# schematic_christmas_tree.net
KiCad netlist of a schematic drawn in Altium Designer
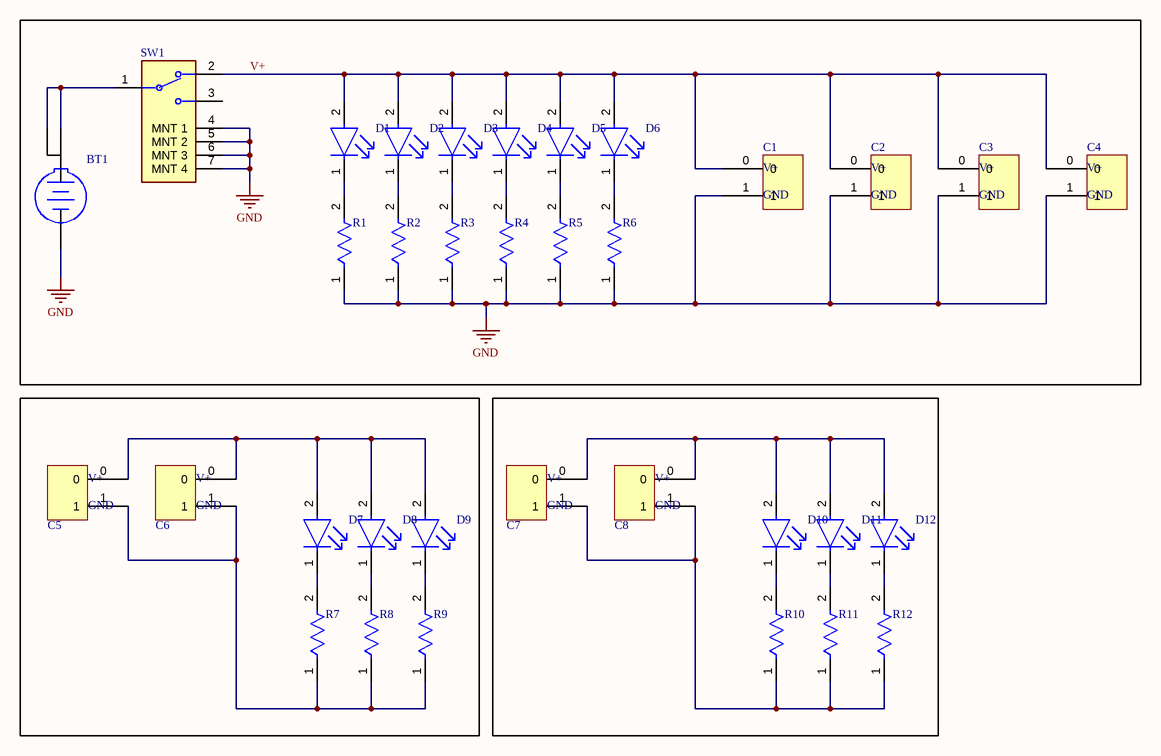
[diagram p0: schematic_christmas_tree.SchDoc]

(export (version "E")
  (design (tool "Eeschema 10.0.6"))
  (components
    (comp (ref "BT1")
      (value "3001")
      (footprint "KSTN-3001_V")
      (description "Holder Battery Coin, 12 mm, 2-Pin THD, RoHS")
      (fields (field (name "MANUFACTURER") "Keystone"))
      (libsource (lib "Altium Content Vault") (part "BATTERY-HOLDER-COIN-3"))
    )
    (comp (ref "C1")
      (value "conn_pcb")
      (footprint "pcb_connector")
      (libsource (lib "connectors") (part "conn_pcb"))
    )
    (comp (ref "C2")
      (value "conn_pcb")
      (footprint "pcb_connector")
      (libsource (lib "connectors") (part "conn_pcb"))
    )
    (comp (ref "C3")
      (value "conn_pcb")
      (footprint "pcb_connector")
      (libsource (lib "connectors") (part "conn_pcb"))
    )
    (comp (ref "C4")
      (value "conn_pcb")
      (footprint "pcb_connector")
      (libsource (lib "connectors") (part "conn_pcb"))
    )
    (comp (ref "C5") (value "conn_pcb") (footprint "pcb_connector") (libsource (lib "") (part "conn_pcb_1")))
    (comp (ref "C6") (value "conn_pcb") (footprint "pcb_connector") (libsource (lib "") (part "conn_pcb_1")))
    (comp (ref "C7") (value "conn_pcb") (footprint "pcb_connector") (libsource (lib "") (part "conn_pcb_1")))
    (comp (ref "C8") (value "conn_pcb") (footprint "pcb_connector") (libsource (lib "") (part "conn_pcb_1")))
    (comp (ref "D1")
      (value "APHCM2012SYCK-F01")
      (footprint "FP-APHCM2012SYCK-F01-MFG")
      (description "LED YELLOW CLEAR CHIP SMD")
      (libsource (lib "Altium Content Vault") (part "8706943c75ba83719d021d2fdc84c58"))
    )
    (comp (ref "D2")
      (value "APHCM2012SYCK-F01")
      (footprint "FP-APHCM2012SYCK-F01-MFG")
      (description "LED YELLOW CLEAR CHIP SMD")
      (libsource (lib "Altium Content Vault") (part "8706943c75ba83719d021d2fdc84c58"))
    )
    (comp (ref "D3")
      (value "APHCM2012SYCK-F01")
      (footprint "FP-APHCM2012SYCK-F01-MFG")
      (description "LED YELLOW CLEAR CHIP SMD")
      (libsource (lib "Altium Content Vault") (part "8706943c75ba83719d021d2fdc84c58"))
    )
    (comp (ref "D4")
      (value "APHCM2012SYCK-F01")
      (footprint "FP-APHCM2012SYCK-F01-MFG")
      (description "LED YELLOW CLEAR CHIP SMD")
      (libsource (lib "Altium Content Vault") (part "8706943c75ba83719d021d2fdc84c58"))
    )
    (comp (ref "D5")
      (value "APHCM2012SYCK-F01")
      (footprint "FP-APHCM2012SYCK-F01-MFG")
      (description "LED YELLOW CLEAR CHIP SMD")
      (libsource (lib "Altium Content Vault") (part "8706943c75ba83719d021d2fdc84c58"))
    )
    (comp (ref "D6")
      (value "APHCM2012SYCK-F01")
      (footprint "FP-APHCM2012SYCK-F01-MFG")
      (description "LED YELLOW CLEAR CHIP SMD")
      (libsource (lib "Altium Content Vault") (part "8706943c75ba83719d021d2fdc84c58"))
    )
    (comp (ref "D7")
      (value "APHCM2012SYCK-F01")
      (footprint "FP-APHCM2012SYCK-F01-MFG")
      (description "LED YELLOW CLEAR CHIP SMD")
      (libsource (lib "Altium Content Vault") (part "8706943c75ba83719d021d2fdc84c58"))
    )
    (comp (ref "D8")
      (value "APHCM2012SYCK-F01")
      (footprint "FP-APHCM2012SYCK-F01-MFG")
      (description "LED YELLOW CLEAR CHIP SMD")
      (libsource (lib "Altium Content Vault") (part "8706943c75ba83719d021d2fdc84c58"))
    )
    (comp (ref "D9")
      (value "APHCM2012SYCK-F01")
      (footprint "FP-APHCM2012SYCK-F01-MFG")
      (description "LED YELLOW CLEAR CHIP SMD")
      (libsource (lib "Altium Content Vault") (part "8706943c75ba83719d021d2fdc84c58"))
    )
    (comp (ref "D10")
      (value "APHCM2012SYCK-F01")
      (footprint "FP-APHCM2012SYCK-F01-MFG")
      (description "LED YELLOW CLEAR CHIP SMD")
      (libsource (lib "Altium Content Vault") (part "8706943c75ba83719d021d2fdc84c58"))
    )
    (comp (ref "D11")
      (value "APHCM2012SYCK-F01")
      (footprint "FP-APHCM2012SYCK-F01-MFG")
      (description "LED YELLOW CLEAR CHIP SMD")
      (libsource (lib "Altium Content Vault") (part "8706943c75ba83719d021d2fdc84c58"))
    )
    (comp (ref "D12")
      (value "APHCM2012SYCK-F01")
      (footprint "FP-APHCM2012SYCK-F01-MFG")
      (description "LED YELLOW CLEAR CHIP SMD")
      (libsource (lib "Altium Content Vault") (part "8706943c75ba83719d021d2fdc84c58"))
    )
    (comp (ref "R1")
      (value "CRCW0603100RJNEA")
      (footprint "FP-CRCW0603-e3-IPC_B")
      (description "RES Thick Film, 100Ω, 5%, 0.1W, 200ppm/°C, 0603")
      (fields (field (name "TOLERANCE") "5%"))
      (libsource (lib "Altium Content Vault") (part "1029c3af85768c4190bb7ad29bc67b5"))
    )
    (comp (ref "R2")
      (value "CRCW0603100RJNEA")
      (footprint "FP-CRCW0603-e3-IPC_B")
      (description "RES Thick Film, 100Ω, 5%, 0.1W, 200ppm/°C, 0603")
      (fields (field (name "TOLERANCE") "5%"))
      (libsource (lib "Altium Content Vault") (part "1029c3af85768c4190bb7ad29bc67b5"))
    )
    (comp (ref "R3")
      (value "CRCW0603100RJNEA")
      (footprint "FP-CRCW0603-e3-IPC_B")
      (description "RES Thick Film, 100Ω, 5%, 0.1W, 200ppm/°C, 0603")
      (fields (field (name "TOLERANCE") "5%"))
      (libsource (lib "Altium Content Vault") (part "1029c3af85768c4190bb7ad29bc67b5"))
    )
    (comp (ref "R4")
      (value "CRCW0603100RJNEA")
      (footprint "FP-CRCW0603-e3-IPC_B")
      (description "RES Thick Film, 100Ω, 5%, 0.1W, 200ppm/°C, 0603")
      (fields (field (name "TOLERANCE") "5%"))
      (libsource (lib "Altium Content Vault") (part "1029c3af85768c4190bb7ad29bc67b5"))
    )
    (comp (ref "R5")
      (value "CRCW0603100RJNEA")
      (footprint "FP-CRCW0603-e3-IPC_B")
      (description "RES Thick Film, 100Ω, 5%, 0.1W, 200ppm/°C, 0603")
      (fields (field (name "TOLERANCE") "5%"))
      (libsource (lib "Altium Content Vault") (part "1029c3af85768c4190bb7ad29bc67b5"))
    )
    (comp (ref "R6")
      (value "CRCW0603100RJNEA")
      (footprint "FP-CRCW0603-e3-IPC_B")
      (description "RES Thick Film, 100Ω, 5%, 0.1W, 200ppm/°C, 0603")
      (fields (field (name "TOLERANCE") "5%"))
      (libsource (lib "Altium Content Vault") (part "1029c3af85768c4190bb7ad29bc67b5"))
    )
    (comp (ref "R7")
      (value "CRCW0603100RJNEA")
      (footprint "FP-CRCW0603-e3-IPC_B")
      (description "RES Thick Film, 100Ω, 5%, 0.1W, 200ppm/°C, 0603")
      (fields (field (name "TOLERANCE") "5%"))
      (libsource (lib "Altium Content Vault") (part "1029c3af85768c4190bb7ad29bc67b5"))
    )
    (comp (ref "R8")
      (value "CRCW0603100RJNEA")
      (footprint "FP-CRCW0603-e3-IPC_B")
      (description "RES Thick Film, 100Ω, 5%, 0.1W, 200ppm/°C, 0603")
      (fields (field (name "TOLERANCE") "5%"))
      (libsource (lib "Altium Content Vault") (part "1029c3af85768c4190bb7ad29bc67b5"))
    )
    (comp (ref "R9")
      (value "CRCW0603100RJNEA")
      (footprint "FP-CRCW0603-e3-IPC_B")
      (description "RES Thick Film, 100Ω, 5%, 0.1W, 200ppm/°C, 0603")
      (fields (field (name "TOLERANCE") "5%"))
      (libsource (lib "Altium Content Vault") (part "1029c3af85768c4190bb7ad29bc67b5"))
    )
    (comp (ref "R10")
      (value "CRCW0603100RJNEA")
      (footprint "FP-CRCW0603-e3-IPC_B")
      (description "RES Thick Film, 100Ω, 5%, 0.1W, 200ppm/°C, 0603")
      (fields (field (name "TOLERANCE") "5%"))
      (libsource (lib "Altium Content Vault") (part "1029c3af85768c4190bb7ad29bc67b5"))
    )
    (comp (ref "R11")
      (value "CRCW0603100RJNEA")
      (footprint "FP-CRCW0603-e3-IPC_B")
      (description "RES Thick Film, 100Ω, 5%, 0.1W, 200ppm/°C, 0603")
      (fields (field (name "TOLERANCE") "5%"))
      (libsource (lib "Altium Content Vault") (part "1029c3af85768c4190bb7ad29bc67b5"))
    )
    (comp (ref "R12")
      (value "CRCW0603100RJNEA")
      (footprint "FP-CRCW0603-e3-IPC_B")
      (description "RES Thick Film, 100Ω, 5%, 0.1W, 200ppm/°C, 0603")
      (fields (field (name "TOLERANCE") "5%"))
      (libsource (lib "Altium Content Vault") (part "1029c3af85768c4190bb7ad29bc67b5"))
    )
    (comp (ref "SW1")
      (value "PCM12SMTR")
      (footprint "FP-PCM12SMTR-MFG")
      (description "SWITCH SLIDE SPDT 300MA 6V")
      (libsource (lib "Altium Content Vault") (part "1a3f67d7e2b5469b171eeab59ffb4d2"))
    )
  )
  (nets
    (net (code "1") (name "/V+") (class "Default")
      (node (ref "C1") (pin "0") (pinfunction "0_0") (pintype "passive"))
      (node (ref "C2") (pin "0") (pinfunction "0_0") (pintype "passive"))
      (node (ref "C3") (pin "0") (pinfunction "0_0") (pintype "passive"))
      (node (ref "C4") (pin "0") (pinfunction "0_0") (pintype "passive"))
      (node (ref "D1") (pin "2") (pinfunction "A_2") (pintype "passive"))
      (node (ref "D2") (pin "2") (pinfunction "A_2") (pintype "passive"))
      (node (ref "D3") (pin "2") (pinfunction "A_2") (pintype "passive"))
      (node (ref "D4") (pin "2") (pinfunction "A_2") (pintype "passive"))
      (node (ref "D5") (pin "2") (pinfunction "A_2") (pintype "passive"))
      (node (ref "D6") (pin "2") (pinfunction "A_2") (pintype "passive"))
      (node (ref "SW1") (pin "2") (pinfunction "2_2") (pintype "passive"))
    )
    (net (code "2") (name "GND") (class "Default")
      (node (ref "BT1") (pin "3") (pinfunction "-_3") (pintype "passive"))
      (node (ref "C1") (pin "1") (pinfunction "1_1") (pintype "passive"))
      (node (ref "C2") (pin "1") (pinfunction "1_1") (pintype "passive"))
      (node (ref "C3") (pin "1") (pinfunction "1_1") (pintype "passive"))
      (node (ref "C4") (pin "1") (pinfunction "1_1") (pintype "passive"))
      (node (ref "R1") (pin "1") (pinfunction "1_1") (pintype "passive"))
      (node (ref "R2") (pin "1") (pinfunction "1_1") (pintype "passive"))
      (node (ref "R3") (pin "1") (pinfunction "1_1") (pintype "passive"))
      (node (ref "R4") (pin "1") (pinfunction "1_1") (pintype "passive"))
      (node (ref "R5") (pin "1") (pinfunction "1_1") (pintype "passive"))
      (node (ref "R6") (pin "1") (pinfunction "1_1") (pintype "passive"))
      (node (ref "SW1") (pin "4") (pinfunction "MNT_1_4") (pintype "passive"))
      (node (ref "SW1") (pin "5") (pinfunction "MNT_2_5") (pintype "passive"))
      (node (ref "SW1") (pin "6") (pinfunction "MNT_3_6") (pintype "passive"))
      (node (ref "SW1") (pin "7") (pinfunction "MNT_4_7") (pintype "passive"))
    )
    (net (code "3") (name "Net-(BT1-+-Pad1)") (class "Default")
      (node (ref "BT1") (pin "1") (pinfunction "+_1") (pintype "passive"))
      (node (ref "BT1") (pin "2") (pinfunction "+_2") (pintype "passive"))
      (node (ref "SW1") (pin "1") (pinfunction "1_1") (pintype "passive"))
    )
    (net (code "4") (name "Net-(C5-Pad1)") (class "Default")
      (node (ref "C5") (pin "1") (pinfunction "1_1") (pintype "passive"))
      (node (ref "C6") (pin "1") (pinfunction "1_1") (pintype "passive"))
      (node (ref "R7") (pin "1") (pinfunction "1_1") (pintype "passive"))
      (node (ref "R8") (pin "1") (pinfunction "1_1") (pintype "passive"))
      (node (ref "R9") (pin "1") (pinfunction "1_1") (pintype "passive"))
    )
    (net (code "5") (name "Net-(C7-Pad1)") (class "Default")
      (node (ref "C7") (pin "1") (pinfunction "1_1") (pintype "passive"))
      (node (ref "C8") (pin "1") (pinfunction "1_1") (pintype "passive"))
      (node (ref "R10") (pin "1") (pinfunction "1_1") (pintype "passive"))
      (node (ref "R11") (pin "1") (pinfunction "1_1") (pintype "passive"))
      (node (ref "R12") (pin "1") (pinfunction "1_1") (pintype "passive"))
    )
    (net (code "6") (name "Net-(D1-C)") (class "Default")
      (node (ref "D1") (pin "1") (pinfunction "C_1") (pintype "passive"))
      (node (ref "R1") (pin "2") (pinfunction "2_2") (pintype "passive"))
    )
    (net (code "7") (name "Net-(D2-C)") (class "Default")
      (node (ref "D2") (pin "1") (pinfunction "C_1") (pintype "passive"))
      (node (ref "R2") (pin "2") (pinfunction "2_2") (pintype "passive"))
    )
    (net (code "8") (name "Net-(D3-C)") (class "Default")
      (node (ref "D3") (pin "1") (pinfunction "C_1") (pintype "passive"))
      (node (ref "R3") (pin "2") (pinfunction "2_2") (pintype "passive"))
    )
    (net (code "9") (name "Net-(D4-C)") (class "Default")
      (node (ref "D4") (pin "1") (pinfunction "C_1") (pintype "passive"))
      (node (ref "R4") (pin "2") (pinfunction "2_2") (pintype "passive"))
    )
    (net (code "10") (name "Net-(D5-C)") (class "Default")
      (node (ref "D5") (pin "1") (pinfunction "C_1") (pintype "passive"))
      (node (ref "R5") (pin "2") (pinfunction "2_2") (pintype "passive"))
    )
    (net (code "11") (name "Net-(D6-C)") (class "Default")
      (node (ref "D6") (pin "1") (pinfunction "C_1") (pintype "passive"))
      (node (ref "R6") (pin "2") (pinfunction "2_2") (pintype "passive"))
    )
    (net (code "12") (name "Net-(D7-A)") (class "Default")
      (node (ref "C5") (pin "0") (pinfunction "0_0") (pintype "passive"))
      (node (ref "C6") (pin "0") (pinfunction "0_0") (pintype "passive"))
      (node (ref "D7") (pin "2") (pinfunction "A_2") (pintype "passive"))
      (node (ref "D8") (pin "2") (pinfunction "A_2") (pintype "passive"))
      (node (ref "D9") (pin "2") (pinfunction "A_2") (pintype "passive"))
    )
    (net (code "13") (name "Net-(D7-C)") (class "Default")
      (node (ref "D7") (pin "1") (pinfunction "C_1") (pintype "passive"))
      (node (ref "R7") (pin "2") (pinfunction "2_2") (pintype "passive"))
    )
    (net (code "14") (name "Net-(D8-C)") (class "Default")
      (node (ref "D8") (pin "1") (pinfunction "C_1") (pintype "passive"))
      (node (ref "R8") (pin "2") (pinfunction "2_2") (pintype "passive"))
    )
    (net (code "15") (name "Net-(D9-C)") (class "Default")
      (node (ref "D9") (pin "1") (pinfunction "C_1") (pintype "passive"))
      (node (ref "R9") (pin "2") (pinfunction "2_2") (pintype "passive"))
    )
    (net (code "16") (name "Net-(D10-A)") (class "Default")
      (node (ref "C7") (pin "0") (pinfunction "0_0") (pintype "passive"))
      (node (ref "C8") (pin "0") (pinfunction "0_0") (pintype "passive"))
      (node (ref "D10") (pin "2") (pinfunction "A_2") (pintype "passive"))
      (node (ref "D11") (pin "2") (pinfunction "A_2") (pintype "passive"))
      (node (ref "D12") (pin "2") (pinfunction "A_2") (pintype "passive"))
    )
    (net (code "17") (name "Net-(D10-C)") (class "Default")
      (node (ref "D10") (pin "1") (pinfunction "C_1") (pintype "passive"))
      (node (ref "R10") (pin "2") (pinfunction "2_2") (pintype "passive"))
    )
    (net (code "18") (name "Net-(D11-C)") (class "Default")
      (node (ref "D11") (pin "1") (pinfunction "C_1") (pintype "passive"))
      (node (ref "R11") (pin "2") (pinfunction "2_2") (pintype "passive"))
    )
    (net (code "19") (name "Net-(D12-C)") (class "Default")
      (node (ref "D12") (pin "1") (pinfunction "C_1") (pintype "passive"))
      (node (ref "R12") (pin "2") (pinfunction "2_2") (pintype "passive"))
    )
    (net (code "20") (name "unconnected-(SW1-Pad3)") (class "Default")
      (node (ref "SW1") (pin "3") (pinfunction "3_3") (pintype "passive"))
    )
  )
)
